# Easycheck_rev2_chip.net
KiCad netlist of a schematic drawn in EAGLE
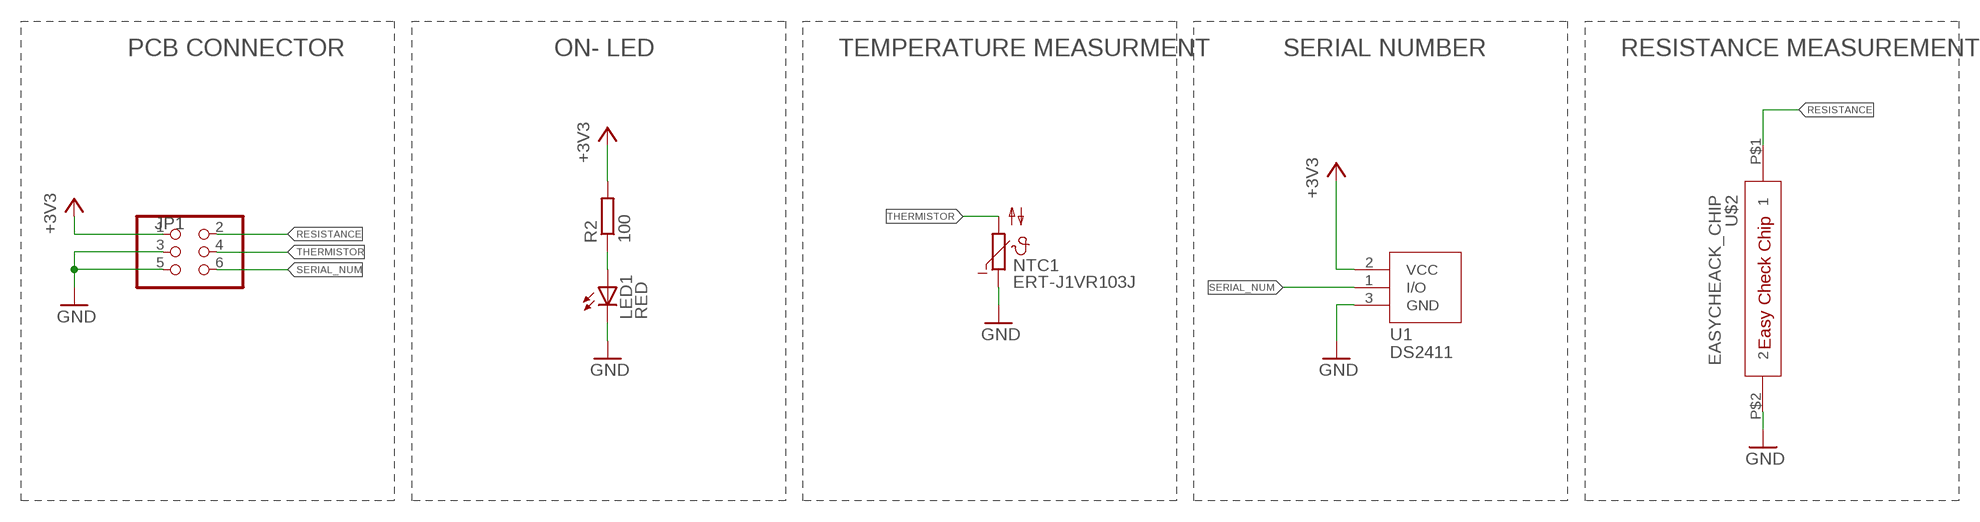
[diagram p0: schematic, sheet 1]

(export (version "E")
  (design (tool "Eeschema 10.0.6"))
  (components
    (comp (ref "JP1")
      (value "PINHD-2X3")
      (footprint "eagle-import:2X03")
      (libsource (lib "eagle-import") (part "PINHD-2X3"))
    )
    (comp (ref "LED1")
      (value "RED")
      (footprint "eagle-import:CHIPLED_0603")
      (libsource (lib "eagle-import") (part "LEDCHIPLED_0603"))
    )
    (comp (ref "NTC1")
      (value "ERT-J1VR103J")
      (footprint "eagle-import:C0603K")
      (libsource (lib "eagle-import") (part "NTC_SMD"))
    )
    (comp (ref "R2")
      (value "100")
      (footprint "eagle-import:R0402")
      (libsource (lib "eagle-import") (part "R-EU_R0402"))
    )
    (comp (ref "U$2")
      (value "EASYCHEACK_CHIP")
      (footprint "eagle-import:EASYCHECK_CHIP")
      (libsource (lib "eagle-import") (part "EASYCHEACK_CHIP"))
    )
    (comp (ref "U1")
      (value "DS2411")
      (footprint "eagle-import:SOT23")
      (libsource (lib "eagle-import") (part "DS2411"))
    )
  )
  (nets
    (net (code "1") (name "+3V3") (class "Default")
      (node (ref "JP1") (pin "1") (pinfunction "1_1") (pintype "passive"))
      (node (ref "R2") (pin "2") (pinfunction "2_2") (pintype "passive"))
      (node (ref "U1") (pin "2") (pinfunction "VCC_2") (pintype "bidirectional"))
    )
    (net (code "2") (name "GND") (class "Default")
      (node (ref "JP1") (pin "3") (pinfunction "3_3") (pintype "passive"))
      (node (ref "JP1") (pin "5") (pinfunction "5_5") (pintype "passive"))
      (node (ref "LED1") (pin "C") (pinfunction "C_C") (pintype "passive"))
      (node (ref "NTC1") (pin "1") (pinfunction "1_1") (pintype "passive"))
      (node (ref "U$2") (pin "P$2") (pinfunction "2_P$2") (pintype "bidirectional"))
      (node (ref "U1") (pin "3") (pinfunction "GND_3") (pintype "bidirectional"))
    )
    (net (code "3") (name "Net-(LED1-PadA)") (class "Default")
      (node (ref "LED1") (pin "A") (pinfunction "A_A") (pintype "passive"))
      (node (ref "R2") (pin "1") (pinfunction "1_1") (pintype "passive"))
    )
    (net (code "4") (name "RESISTANCE") (class "Default")
      (node (ref "JP1") (pin "2") (pinfunction "2_2") (pintype "passive"))
      (node (ref "U$2") (pin "P$1") (pinfunction "1_P$1") (pintype "bidirectional"))
    )
    (net (code "5") (name "SERIAL_NUM") (class "Default")
      (node (ref "JP1") (pin "6") (pinfunction "6_6") (pintype "passive"))
      (node (ref "U1") (pin "1") (pinfunction "I/O_1") (pintype "bidirectional"))
    )
    (net (code "6") (name "THERMISTOR") (class "Default")
      (node (ref "JP1") (pin "4") (pinfunction "4_4") (pintype "passive"))
      (node (ref "NTC1") (pin "2") (pinfunction "2_2") (pintype "passive"))
    )
  )
)
